# tdoa_4011_decotec.net
KiCad netlist of a schematic drawn in EAGLE
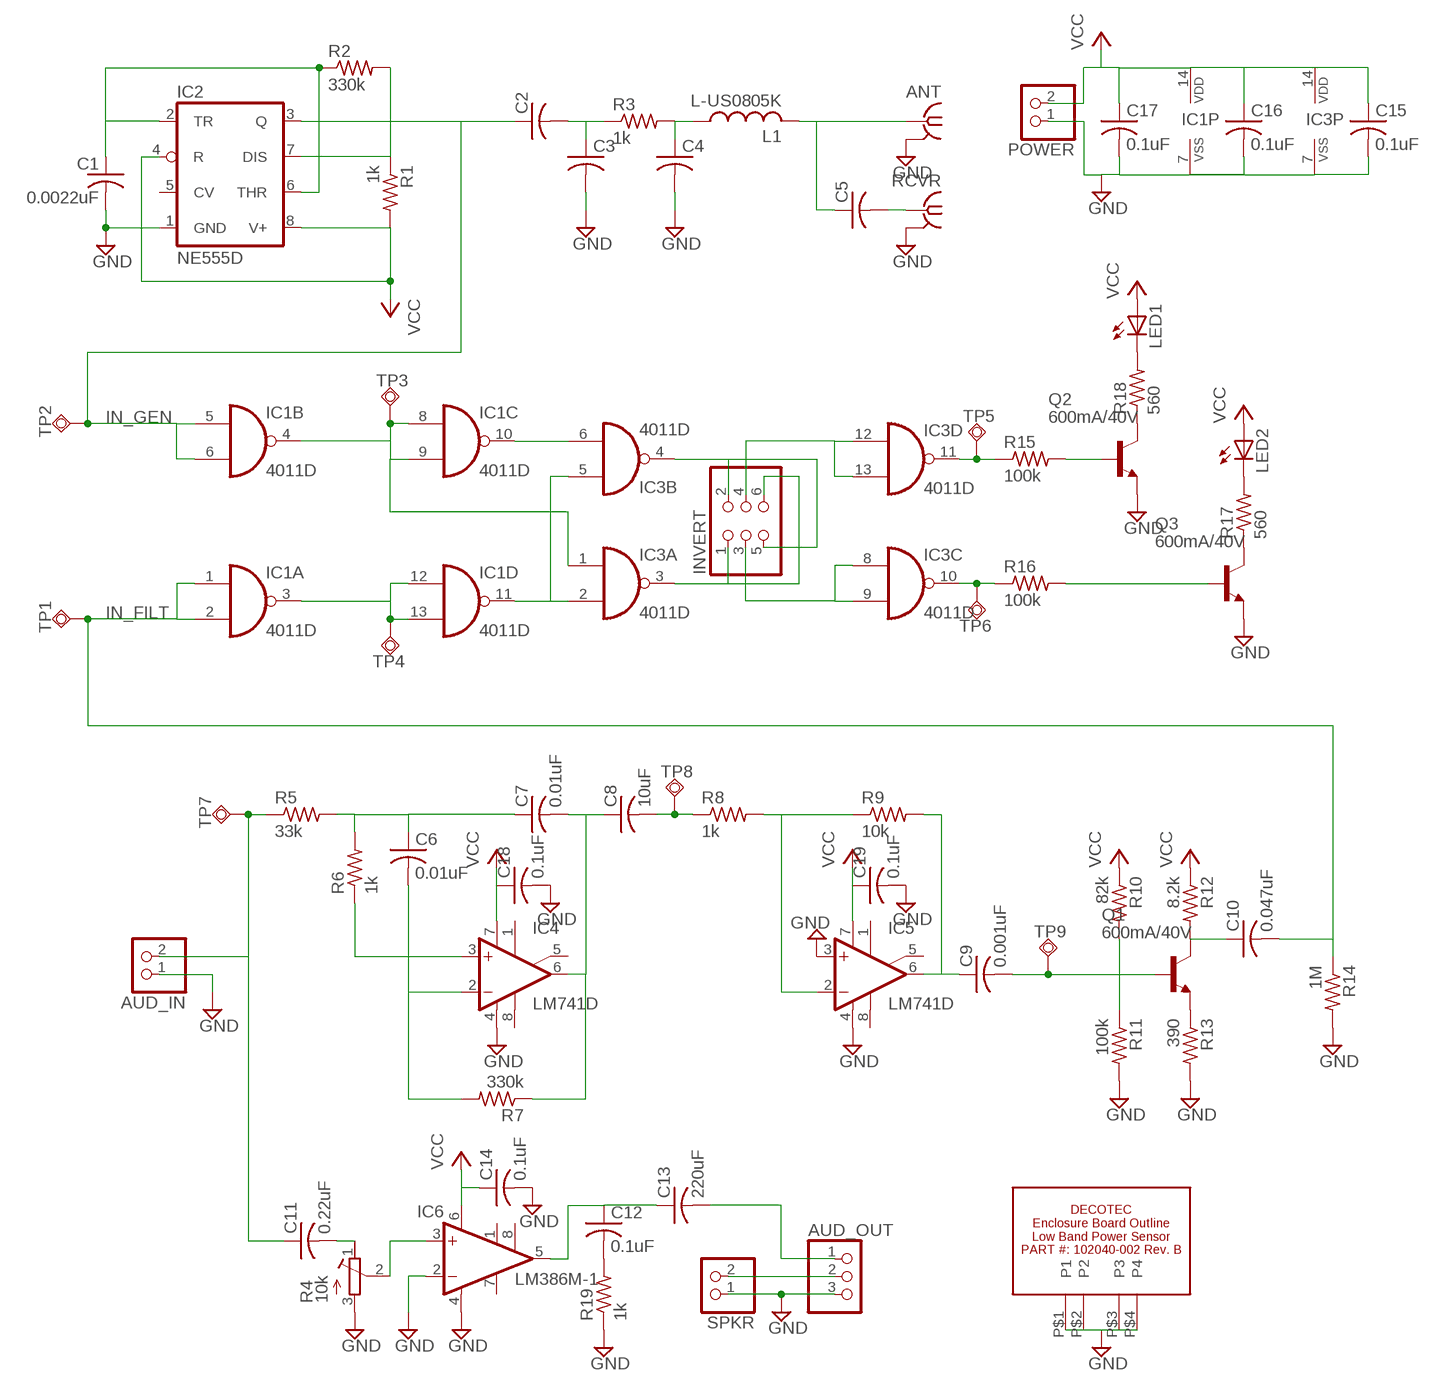
[diagram p0: schematic, sheet 1]

(export (version "E")
  (design (tool "Eeschema 10.0.6"))
  (components
    (comp (ref "ANT")
      (value "SMA-142-0701-801/806")
      (footprint "eagle-import:J502-ND-142-0701-801_806")
      (fields (field (name "MF") "JOHNSON COMPONENTS") (field (name "MPN") "142-0701-801"))
      (libsource (lib "eagle-import") (part "SMA-142-0701-801/806"))
    )
    (comp (ref "AUD_IN")
      (value "PINHD-1X2")
      (footprint "eagle-import:1X02")
      (libsource (lib "eagle-import") (part "PINHD-1X2"))
    )
    (comp (ref "AUD_OUT")
      (value "PINHD-1X3")
      (footprint "eagle-import:1X03")
      (libsource (lib "eagle-import") (part "PINHD-1X3"))
    )
    (comp (ref "C1")
      (value "0.0022uF")
      (footprint "eagle-import:C0805K")
      (libsource (lib "eagle-import") (part "C-USC0805K"))
    )
    (comp (ref "C2")
      (value "C-USC0805K")
      (footprint "eagle-import:C0805K")
      (libsource (lib "eagle-import") (part "C-USC0805K"))
    )
    (comp (ref "C3")
      (value "C-USC0805K")
      (footprint "eagle-import:C0805K")
      (libsource (lib "eagle-import") (part "C-USC0805K"))
    )
    (comp (ref "C4")
      (value "C-USC0805K")
      (footprint "eagle-import:C0805K")
      (libsource (lib "eagle-import") (part "C-USC0805K"))
    )
    (comp (ref "C5")
      (value "C-USC0805K")
      (footprint "eagle-import:C0805K")
      (libsource (lib "eagle-import") (part "C-USC0805K"))
    )
    (comp (ref "C6")
      (value "0.01uF")
      (footprint "eagle-import:C0805K")
      (libsource (lib "eagle-import") (part "C-USC0805K"))
    )
    (comp (ref "C7")
      (value "0.01uF")
      (footprint "eagle-import:C0805K")
      (libsource (lib "eagle-import") (part "C-USC0805K"))
    )
    (comp (ref "C8")
      (value "10uF")
      (footprint "eagle-import:C0805K")
      (libsource (lib "eagle-import") (part "C-USC0805K"))
    )
    (comp (ref "C9")
      (value "0.001uF")
      (footprint "eagle-import:C0805K")
      (libsource (lib "eagle-import") (part "C-USC0805K"))
    )
    (comp (ref "C10")
      (value "0.047uF")
      (footprint "eagle-import:C0805K")
      (libsource (lib "eagle-import") (part "C-USC0805K"))
    )
    (comp (ref "C11")
      (value "0.22uF")
      (footprint "eagle-import:C0805K")
      (libsource (lib "eagle-import") (part "C-USC0805K"))
    )
    (comp (ref "C12")
      (value "0.1uF")
      (footprint "eagle-import:C0805K")
      (libsource (lib "eagle-import") (part "C-USC0805K"))
    )
    (comp (ref "C13")
      (value "220uF")
      (footprint "eagle-import:C0805K")
      (libsource (lib "eagle-import") (part "C-USC0805K"))
    )
    (comp (ref "C14")
      (value "0.1uF")
      (footprint "eagle-import:C0805K")
      (libsource (lib "eagle-import") (part "C-USC0805K"))
    )
    (comp (ref "C15")
      (value "0.1uF")
      (footprint "eagle-import:C0805K")
      (libsource (lib "eagle-import") (part "C-USC0805K"))
    )
    (comp (ref "C16")
      (value "0.1uF")
      (footprint "eagle-import:C0805K")
      (libsource (lib "eagle-import") (part "C-USC0805K"))
    )
    (comp (ref "C17")
      (value "0.1uF")
      (footprint "eagle-import:C0805K")
      (libsource (lib "eagle-import") (part "C-USC0805K"))
    )
    (comp (ref "C18")
      (value "0.1uF")
      (footprint "eagle-import:C0805K")
      (libsource (lib "eagle-import") (part "C-USC0805K"))
    )
    (comp (ref "C19")
      (value "0.1uF")
      (footprint "eagle-import:C0805K")
      (libsource (lib "eagle-import") (part "C-USC0805K"))
    )
    (comp (ref "IC1")
      (value "4011D")
      (footprint "eagle-import:SO14")
      (libsource (lib "eagle-import") (part "4011D"))
    )
    (comp (ref "IC2")
      (value "NE555D")
      (footprint "eagle-import:SO08")
      (libsource (lib "eagle-import") (part "555DNE"))
    )
    (comp (ref "IC3")
      (value "4011D")
      (footprint "eagle-import:SO14")
      (libsource (lib "eagle-import") (part "4011D"))
    )
    (comp (ref "IC4")
      (value "LM741D")
      (footprint "eagle-import:SO08")
      (libsource (lib "eagle-import") (part "741DLM"))
    )
    (comp (ref "IC5")
      (value "LM741D")
      (footprint "eagle-import:SO08")
      (libsource (lib "eagle-import") (part "741DLM"))
    )
    (comp (ref "IC6")
      (value "LM386M-1")
      (footprint "eagle-import:SO08")
      (libsource (lib "eagle-import") (part "LM386?-M1"))
    )
    (comp (ref "INVERT")
      (value "PINHD-2X3")
      (footprint "eagle-import:2X03")
      (libsource (lib "eagle-import") (part "PINHD-2X3"))
    )
    (comp (ref "L1")
      (value "L-US0805K")
      (footprint "eagle-import:C0805K")
      (libsource (lib "eagle-import") (part "L-US0805K"))
    )
    (comp (ref "LED1")
      (value "LED3MM")
      (footprint "eagle-import:LED3MM")
      (libsource (lib "eagle-import") (part "LED3MM"))
    )
    (comp (ref "LED2")
      (value "LED3MM")
      (footprint "eagle-import:LED3MM")
      (libsource (lib "eagle-import") (part "LED3MM"))
    )
    (comp (ref "POWER")
      (value "PINHD-1X2")
      (footprint "eagle-import:1X02")
      (libsource (lib "eagle-import") (part "PINHD-1X2"))
    )
    (comp (ref "Q1")
      (value "600mA/40V")
      (footprint "eagle-import:SOT23-BEC")
      (libsource (lib "eagle-import") (part "-NPN-SOT23-BECMMBT3904LT1"))
    )
    (comp (ref "Q2")
      (value "600mA/40V")
      (footprint "eagle-import:SOT23-BEC")
      (libsource (lib "eagle-import") (part "-NPN-SOT23-BECMMBT3904LT1"))
    )
    (comp (ref "Q3")
      (value "600mA/40V")
      (footprint "eagle-import:SOT23-BEC")
      (libsource (lib "eagle-import") (part "-NPN-SOT23-BECMMBT3904LT1"))
    )
    (comp (ref "R1")
      (value "1k")
      (footprint "eagle-import:R0805")
      (libsource (lib "eagle-import") (part "R-US_R0805"))
    )
    (comp (ref "R2")
      (value "330k")
      (footprint "eagle-import:R0805")
      (libsource (lib "eagle-import") (part "R-US_R0805"))
    )
    (comp (ref "R3")
      (value "1k")
      (footprint "eagle-import:R0805")
      (libsource (lib "eagle-import") (part "R-US_R0805"))
    )
    (comp (ref "R4")
      (value "10k")
      (footprint "eagle-import:RTRIM3314G")
      (libsource (lib "eagle-import") (part "R-TRIMM3314G"))
    )
    (comp (ref "R5")
      (value "33k")
      (footprint "eagle-import:R0805")
      (libsource (lib "eagle-import") (part "R-US_R0805"))
    )
    (comp (ref "R6")
      (value "1k")
      (footprint "eagle-import:R0805")
      (libsource (lib "eagle-import") (part "R-US_R0805"))
    )
    (comp (ref "R7")
      (value "330k")
      (footprint "eagle-import:R0805")
      (libsource (lib "eagle-import") (part "R-US_R0805"))
    )
    (comp (ref "R8")
      (value "1k")
      (footprint "eagle-import:R0805")
      (libsource (lib "eagle-import") (part "R-US_R0805"))
    )
    (comp (ref "R9")
      (value "10k")
      (footprint "eagle-import:R0805")
      (libsource (lib "eagle-import") (part "R-US_R0805"))
    )
    (comp (ref "R10")
      (value "82k")
      (footprint "eagle-import:R0805")
      (libsource (lib "eagle-import") (part "R-US_R0805"))
    )
    (comp (ref "R11")
      (value "100k")
      (footprint "eagle-import:R0805")
      (libsource (lib "eagle-import") (part "R-US_R0805"))
    )
    (comp (ref "R12")
      (value "8.2k")
      (footprint "eagle-import:R0805")
      (libsource (lib "eagle-import") (part "R-US_R0805"))
    )
    (comp (ref "R13")
      (value "390")
      (footprint "eagle-import:R0805")
      (libsource (lib "eagle-import") (part "R-US_R0805"))
    )
    (comp (ref "R14")
      (value "1M")
      (footprint "eagle-import:R0805")
      (libsource (lib "eagle-import") (part "R-US_R0805"))
    )
    (comp (ref "R15")
      (value "100k")
      (footprint "eagle-import:R0805")
      (libsource (lib "eagle-import") (part "R-US_R0805"))
    )
    (comp (ref "R16")
      (value "100k")
      (footprint "eagle-import:R0805")
      (libsource (lib "eagle-import") (part "R-US_R0805"))
    )
    (comp (ref "R17")
      (value "560")
      (footprint "eagle-import:R0805")
      (libsource (lib "eagle-import") (part "R-US_R0805"))
    )
    (comp (ref "R18")
      (value "560")
      (footprint "eagle-import:R0805")
      (libsource (lib "eagle-import") (part "R-US_R0805"))
    )
    (comp (ref "R19")
      (value "1k")
      (footprint "eagle-import:R0805")
      (libsource (lib "eagle-import") (part "R-US_R0805"))
    )
    (comp (ref "RCVR")
      (value "SMA-142-0701-801/806")
      (footprint "eagle-import:J502-ND-142-0701-801_806")
      (fields (field (name "MF") "JOHNSON COMPONENTS") (field (name "MPN") "142-0701-801"))
      (libsource (lib "eagle-import") (part "SMA-142-0701-801/806"))
    )
    (comp (ref "SPKR")
      (value "PINHD-1X2")
      (footprint "eagle-import:1X02")
      (libsource (lib "eagle-import") (part "PINHD-1X2"))
    )
    (comp (ref "TP1")
      (value "TPSQTP20SQ")
      (footprint "eagle-import:TP20SQ")
      (libsource (lib "eagle-import") (part "TPSQTP20SQ"))
    )
    (comp (ref "TP2")
      (value "TPSQTP20SQ")
      (footprint "eagle-import:TP20SQ")
      (libsource (lib "eagle-import") (part "TPSQTP20SQ"))
    )
    (comp (ref "TP3")
      (value "TPSQTP20SQ")
      (footprint "eagle-import:TP20SQ")
      (libsource (lib "eagle-import") (part "TPSQTP20SQ"))
    )
    (comp (ref "TP4")
      (value "TPSQTP20SQ")
      (footprint "eagle-import:TP20SQ")
      (libsource (lib "eagle-import") (part "TPSQTP20SQ"))
    )
    (comp (ref "TP5")
      (value "TPSQTP20SQ")
      (footprint "eagle-import:TP20SQ")
      (libsource (lib "eagle-import") (part "TPSQTP20SQ"))
    )
    (comp (ref "TP6")
      (value "TPSQTP20SQ")
      (footprint "eagle-import:TP20SQ")
      (libsource (lib "eagle-import") (part "TPSQTP20SQ"))
    )
    (comp (ref "TP7")
      (value "TPSQTP20SQ")
      (footprint "eagle-import:TP20SQ")
      (libsource (lib "eagle-import") (part "TPSQTP20SQ"))
    )
    (comp (ref "TP8")
      (value "TPSQTP20SQ")
      (footprint "eagle-import:TP20SQ")
      (libsource (lib "eagle-import") (part "TPSQTP20SQ"))
    )
    (comp (ref "TP9")
      (value "TPSQTP20SQ")
      (footprint "eagle-import:TP20SQ")
      (libsource (lib "eagle-import") (part "TPSQTP20SQ"))
    )
    (comp (ref "U$1")
      (value "DECOTEC_102040-002B")
      (footprint "eagle-import:DECOTEC_102040-002B")
      (libsource (lib "eagle-import") (part "DECOTEC_102040-002B"))
    )
  )
  (nets
    (net (code "1") (name "/IN_FILT") (class "Default")
      (node (ref "C10") (pin "2") (pinfunction "2_2") (pintype "passive"))
      (node (ref "IC1") (pin "1") (pinfunction "I0_1") (pintype "input"))
      (node (ref "IC1") (pin "2") (pinfunction "I1_2") (pintype "input"))
      (node (ref "R14") (pin "1") (pinfunction "1_1") (pintype "passive"))
      (node (ref "TP1") (pin "TP") (pinfunction "TP_TP") (pintype "input"))
    )
    (net (code "2") (name "/IN_GEN") (class "Default")
      (node (ref "C2") (pin "1") (pinfunction "1_1") (pintype "passive"))
      (node (ref "IC1") (pin "5") (pinfunction "I0_5") (pintype "input"))
      (node (ref "IC1") (pin "6") (pinfunction "I1_6") (pintype "input"))
      (node (ref "IC2") (pin "3") (pinfunction "Q_3") (pintype "output"))
      (node (ref "TP2") (pin "TP") (pinfunction "TP_TP") (pintype "input"))
    )
    (net (code "3") (name "GND") (class "Default")
      (node (ref "ANT") (pin "G@1") (pinfunction "2_G@1") (pintype "passive"))
      (node (ref "ANT") (pin "G@2") (pinfunction "2_G@2") (pintype "passive"))
      (node (ref "ANT") (pin "G@3") (pinfunction "2_G@3") (pintype "passive"))
      (node (ref "ANT") (pin "G@4") (pinfunction "2_G@4") (pintype "passive"))
      (node (ref "AUD_IN") (pin "1") (pinfunction "1_1") (pintype "passive"))
      (node (ref "AUD_OUT") (pin "3") (pinfunction "3_3") (pintype "passive"))
      (node (ref "C1") (pin "2") (pinfunction "2_2") (pintype "passive"))
      (node (ref "C14") (pin "2") (pinfunction "2_2") (pintype "passive"))
      (node (ref "C15") (pin "2") (pinfunction "2_2") (pintype "passive"))
      (node (ref "C16") (pin "2") (pinfunction "2_2") (pintype "passive"))
      (node (ref "C17") (pin "2") (pinfunction "2_2") (pintype "passive"))
      (node (ref "C18") (pin "2") (pinfunction "2_2") (pintype "passive"))
      (node (ref "C19") (pin "2") (pinfunction "2_2") (pintype "passive"))
      (node (ref "C3") (pin "2") (pinfunction "2_2") (pintype "passive"))
      (node (ref "C4") (pin "2") (pinfunction "2_2") (pintype "passive"))
      (node (ref "IC1") (pin "7") (pinfunction "VSS_7") (pintype "power_in"))
      (node (ref "IC2") (pin "1") (pinfunction "GND_1") (pintype "power_in"))
      (node (ref "IC3") (pin "7") (pinfunction "VSS_7") (pintype "power_in"))
      (node (ref "IC4") (pin "4") (pinfunction "V-_4") (pintype "power_in"))
      (node (ref "IC5") (pin "3") (pinfunction "+IN_3") (pintype "input"))
      (node (ref "IC5") (pin "4") (pinfunction "V-_4") (pintype "power_in"))
      (node (ref "IC6") (pin "2") (pinfunction "-IN_2") (pintype "input"))
      (node (ref "IC6") (pin "4") (pinfunction "GND_4") (pintype "power_in"))
      (node (ref "POWER") (pin "1") (pinfunction "1_1") (pintype "passive"))
      (node (ref "Q2") (pin "E") (pinfunction "E_E") (pintype "passive"))
      (node (ref "Q3") (pin "E") (pinfunction "E_E") (pintype "passive"))
      (node (ref "R11") (pin "2") (pinfunction "2_2") (pintype "passive"))
      (node (ref "R13") (pin "2") (pinfunction "2_2") (pintype "passive"))
      (node (ref "R14") (pin "2") (pinfunction "2_2") (pintype "passive"))
      (node (ref "R19") (pin "1") (pinfunction "1_1") (pintype "passive"))
      (node (ref "R4") (pin "3") (pinfunction "A_3") (pintype "passive"))
      (node (ref "RCVR") (pin "G@1") (pinfunction "2_G@1") (pintype "passive"))
      (node (ref "RCVR") (pin "G@2") (pinfunction "2_G@2") (pintype "passive"))
      (node (ref "RCVR") (pin "G@3") (pinfunction "2_G@3") (pintype "passive"))
      (node (ref "RCVR") (pin "G@4") (pinfunction "2_G@4") (pintype "passive"))
      (node (ref "SPKR") (pin "1") (pinfunction "1_1") (pintype "passive"))
      (node (ref "U$1") (pin "P$1") (pinfunction "P1_P$1") (pintype "bidirectional"))
      (node (ref "U$1") (pin "P$2") (pinfunction "P2_P$2") (pintype "bidirectional"))
      (node (ref "U$1") (pin "P$3") (pinfunction "P3_P$3") (pintype "bidirectional"))
      (node (ref "U$1") (pin "P$4") (pinfunction "P4_P$4") (pintype "bidirectional"))
    )
    (net (code "4") (name "Net-(ANT-Pad1)") (class "Default")
      (node (ref "ANT") (pin "1") (pinfunction "1_1") (pintype "passive"))
      (node (ref "C5") (pin "1") (pinfunction "1_1") (pintype "passive"))
      (node (ref "L1") (pin "2") (pinfunction "2_2") (pintype "passive"))
    )
    (net (code "5") (name "Net-(AUD_IN-Pad2)") (class "Default")
      (node (ref "AUD_IN") (pin "2") (pinfunction "2_2") (pintype "passive"))
      (node (ref "C11") (pin "1") (pinfunction "1_1") (pintype "passive"))
      (node (ref "R5") (pin "1") (pinfunction "1_1") (pintype "passive"))
      (node (ref "TP7") (pin "TP") (pinfunction "TP_TP") (pintype "input"))
    )
    (net (code "6") (name "Net-(AUD_OUT-Pad1)") (class "Default")
      (node (ref "AUD_OUT") (pin "1") (pinfunction "1_1") (pintype "passive"))
      (node (ref "C13") (pin "2") (pinfunction "2_2") (pintype "passive"))
    )
    (net (code "7") (name "Net-(AUD_OUT-Pad2)") (class "Default")
      (node (ref "AUD_OUT") (pin "2") (pinfunction "2_2") (pintype "passive"))
      (node (ref "SPKR") (pin "2") (pinfunction "2_2") (pintype "passive"))
    )
    (net (code "8") (name "Net-(C2-Pad2)") (class "Default")
      (node (ref "C2") (pin "2") (pinfunction "2_2") (pintype "passive"))
      (node (ref "C3") (pin "1") (pinfunction "1_1") (pintype "passive"))
      (node (ref "R3") (pin "1") (pinfunction "1_1") (pintype "passive"))
    )
    (net (code "9") (name "Net-(C4-Pad1)") (class "Default")
      (node (ref "C4") (pin "1") (pinfunction "1_1") (pintype "passive"))
      (node (ref "L1") (pin "1") (pinfunction "1_1") (pintype "passive"))
      (node (ref "R3") (pin "2") (pinfunction "2_2") (pintype "passive"))
    )
    (net (code "10") (name "Net-(C5-Pad2)") (class "Default")
      (node (ref "C5") (pin "2") (pinfunction "2_2") (pintype "passive"))
      (node (ref "RCVR") (pin "1") (pinfunction "1_1") (pintype "passive"))
    )
    (net (code "11") (name "Net-(C6-Pad1)") (class "Default")
      (node (ref "C6") (pin "1") (pinfunction "1_1") (pintype "passive"))
      (node (ref "C7") (pin "1") (pinfunction "1_1") (pintype "passive"))
      (node (ref "R5") (pin "2") (pinfunction "2_2") (pintype "passive"))
      (node (ref "R6") (pin "2") (pinfunction "2_2") (pintype "passive"))
    )
    (net (code "12") (name "Net-(C8-Pad2)") (class "Default")
      (node (ref "C8") (pin "2") (pinfunction "2_2") (pintype "passive"))
      (node (ref "R8") (pin "1") (pinfunction "1_1") (pintype "passive"))
      (node (ref "TP8") (pin "TP") (pinfunction "TP_TP") (pintype "input"))
    )
    (net (code "13") (name "Net-(C9-Pad2)") (class "Default")
      (node (ref "C9") (pin "2") (pinfunction "2_2") (pintype "passive"))
      (node (ref "Q1") (pin "B") (pinfunction "B_B") (pintype "passive"))
      (node (ref "R10") (pin "2") (pinfunction "2_2") (pintype "passive"))
      (node (ref "R11") (pin "1") (pinfunction "1_1") (pintype "passive"))
      (node (ref "TP9") (pin "TP") (pinfunction "TP_TP") (pintype "input"))
    )
    (net (code "14") (name "Net-(C10-Pad1)") (class "Default")
      (node (ref "C10") (pin "1") (pinfunction "1_1") (pintype "passive"))
      (node (ref "Q1") (pin "C") (pinfunction "C_C") (pintype "passive"))
      (node (ref "R12") (pin "2") (pinfunction "2_2") (pintype "passive"))
    )
    (net (code "15") (name "Net-(C12-Pad2)") (class "Default")
      (node (ref "C12") (pin "2") (pinfunction "2_2") (pintype "passive"))
      (node (ref "R19") (pin "2") (pinfunction "2_2") (pintype "passive"))
    )
    (net (code "16") (name "Net-(IC1A-O)") (class "Default")
      (node (ref "IC1") (pin "12") (pinfunction "I0_12") (pintype "input"))
      (node (ref "IC1") (pin "13") (pinfunction "I1_13") (pintype "input"))
      (node (ref "IC1") (pin "3") (pinfunction "O_3") (pintype "output"))
      (node (ref "TP4") (pin "TP") (pinfunction "TP_TP") (pintype "input"))
    )
    (net (code "17") (name "Net-(IC1B-O)") (class "Default")
      (node (ref "IC1") (pin "4") (pinfunction "O_4") (pintype "output"))
      (node (ref "IC1") (pin "8") (pinfunction "I0_8") (pintype "input"))
      (node (ref "IC1") (pin "9") (pinfunction "I1_9") (pintype "input"))
      (node (ref "IC3") (pin "1") (pinfunction "I0_1") (pintype "input"))
      (node (ref "TP3") (pin "TP") (pinfunction "TP_TP") (pintype "input"))
    )
    (net (code "18") (name "Net-(IC1C-O)") (class "Default")
      (node (ref "IC1") (pin "10") (pinfunction "O_10") (pintype "output"))
      (node (ref "IC3") (pin "6") (pinfunction "I1_6") (pintype "input"))
    )
    (net (code "19") (name "Net-(IC1D-O)") (class "Default")
      (node (ref "IC1") (pin "11") (pinfunction "O_11") (pintype "output"))
      (node (ref "IC3") (pin "2") (pinfunction "I1_2") (pintype "input"))
      (node (ref "IC3") (pin "5") (pinfunction "I0_5") (pintype "input"))
    )
    (net (code "20") (name "Net-(IC2-DIS)") (class "Default")
      (node (ref "IC2") (pin "7") (pinfunction "DIS_7") (pintype "input"))
      (node (ref "R1") (pin "1") (pinfunction "1_1") (pintype "passive"))
      (node (ref "R2") (pin "2") (pinfunction "2_2") (pintype "passive"))
    )
    (net (code "21") (name "Net-(IC2-THR)") (class "Default")
      (node (ref "C1") (pin "1") (pinfunction "1_1") (pintype "passive"))
      (node (ref "IC2") (pin "2") (pinfunction "TR_2") (pintype "input"))
      (node (ref "IC2") (pin "6") (pinfunction "THR_6") (pintype "input"))
      (node (ref "R2") (pin "1") (pinfunction "1_1") (pintype "passive"))
    )
    (net (code "22") (name "Net-(IC3A-O)") (class "Default")
      (node (ref "IC3") (pin "3") (pinfunction "O_3") (pintype "output"))
      (node (ref "INVERT") (pin "1") (pinfunction "1_1") (pintype "passive"))
      (node (ref "INVERT") (pin "6") (pinfunction "6_6") (pintype "passive"))
    )
    (net (code "23") (name "Net-(IC3B-O)") (class "Default")
      (node (ref "IC3") (pin "4") (pinfunction "O_4") (pintype "output"))
      (node (ref "INVERT") (pin "2") (pinfunction "2_2") (pintype "passive"))
      (node (ref "INVERT") (pin "5") (pinfunction "5_5") (pintype "passive"))
    )
    (net (code "24") (name "Net-(IC3C-I0)") (class "Default")
      (node (ref "IC3") (pin "8") (pinfunction "I0_8") (pintype "input"))
      (node (ref "IC3") (pin "9") (pinfunction "I1_9") (pintype "input"))
      (node (ref "INVERT") (pin "3") (pinfunction "3_3") (pintype "passive"))
    )
    (net (code "25") (name "Net-(IC3C-O)") (class "Default")
      (node (ref "IC3") (pin "10") (pinfunction "O_10") (pintype "output"))
      (node (ref "R16") (pin "1") (pinfunction "1_1") (pintype "passive"))
      (node (ref "TP6") (pin "TP") (pinfunction "TP_TP") (pintype "input"))
    )
    (net (code "26") (name "Net-(IC3D-I0)") (class "Default")
      (node (ref "IC3") (pin "12") (pinfunction "I0_12") (pintype "input"))
      (node (ref "IC3") (pin "13") (pinfunction "I1_13") (pintype "input"))
      (node (ref "INVERT") (pin "4") (pinfunction "4_4") (pintype "passive"))
    )
    (net (code "27") (name "Net-(IC3D-O)") (class "Default")
      (node (ref "IC3") (pin "11") (pinfunction "O_11") (pintype "output"))
      (node (ref "R15") (pin "1") (pinfunction "1_1") (pintype "passive"))
      (node (ref "TP5") (pin "TP") (pinfunction "TP_TP") (pintype "input"))
    )
    (net (code "28") (name "Net-(IC4-+IN)") (class "Default")
      (node (ref "IC4") (pin "3") (pinfunction "+IN_3") (pintype "input"))
      (node (ref "R6") (pin "1") (pinfunction "1_1") (pintype "passive"))
    )
    (net (code "29") (name "Net-(IC4--IN)") (class "Default")
      (node (ref "C6") (pin "2") (pinfunction "2_2") (pintype "passive"))
      (node (ref "IC4") (pin "2") (pinfunction "-IN_2") (pintype "input"))
      (node (ref "R7") (pin "2") (pinfunction "2_2") (pintype "passive"))
    )
    (net (code "30") (name "Net-(IC4-OUT)") (class "Default")
      (node (ref "C7") (pin "2") (pinfunction "2_2") (pintype "passive"))
      (node (ref "C8") (pin "1") (pinfunction "1_1") (pintype "passive"))
      (node (ref "IC4") (pin "6") (pinfunction "OUT_6") (pintype "output"))
      (node (ref "R7") (pin "1") (pinfunction "1_1") (pintype "passive"))
    )
    (net (code "31") (name "Net-(IC5--IN)") (class "Default")
      (node (ref "IC5") (pin "2") (pinfunction "-IN_2") (pintype "input"))
      (node (ref "R8") (pin "2") (pinfunction "2_2") (pintype "passive"))
      (node (ref "R9") (pin "1") (pinfunction "1_1") (pintype "passive"))
    )
    (net (code "32") (name "Net-(IC5-OUT)") (class "Default")
      (node (ref "C9") (pin "1") (pinfunction "1_1") (pintype "passive"))
      (node (ref "IC5") (pin "6") (pinfunction "OUT_6") (pintype "output"))
      (node (ref "R9") (pin "2") (pinfunction "2_2") (pintype "passive"))
    )
    (net (code "33") (name "Net-(IC6-+IN)") (class "Default")
      (node (ref "IC6") (pin "3") (pinfunction "+IN_3") (pintype "input"))
      (node (ref "R4") (pin "2") (pinfunction "S_2") (pintype "passive"))
    )
    (net (code "34") (name "Net-(IC6-OUT)") (class "Default")
      (node (ref "C12") (pin "1") (pinfunction "1_1") (pintype "passive"))
      (node (ref "C13") (pin "1") (pinfunction "1_1") (pintype "passive"))
      (node (ref "IC6") (pin "5") (pinfunction "OUT_5") (pintype "output"))
    )
    (net (code "35") (name "Net-(LED1-C)") (class "Default")
      (node (ref "LED1") (pin "K") (pinfunction "C_K") (pintype "passive"))
      (node (ref "R18") (pin "2") (pinfunction "2_2") (pintype "passive"))
    )
    (net (code "36") (name "Net-(LED2-C)") (class "Default")
      (node (ref "LED2") (pin "K") (pinfunction "C_K") (pintype "passive"))
      (node (ref "R17") (pin "2") (pinfunction "2_2") (pintype "passive"))
    )
    (net (code "37") (name "Net-(Q1-PadE)") (class "Default")
      (node (ref "Q1") (pin "E") (pinfunction "E_E") (pintype "passive"))
      (node (ref "R13") (pin "1") (pinfunction "1_1") (pintype "passive"))
    )
    (net (code "38") (name "Net-(Q2-PadB)") (class "Default")
      (node (ref "Q2") (pin "B") (pinfunction "B_B") (pintype "passive"))
      (node (ref "R15") (pin "2") (pinfunction "2_2") (pintype "passive"))
    )
    (net (code "39") (name "Net-(Q2-PadC)") (class "Default")
      (node (ref "Q2") (pin "C") (pinfunction "C_C") (pintype "passive"))
      (node (ref "R18") (pin "1") (pinfunction "1_1") (pintype "passive"))
    )
    (net (code "40") (name "Net-(Q3-PadB)") (class "Default")
      (node (ref "Q3") (pin "B") (pinfunction "B_B") (pintype "passive"))
      (node (ref "R16") (pin "2") (pinfunction "2_2") (pintype "passive"))
    )
    (net (code "41") (name "Net-(Q3-PadC)") (class "Default")
      (node (ref "Q3") (pin "C") (pinfunction "C_C") (pintype "passive"))
      (node (ref "R17") (pin "1") (pinfunction "1_1") (pintype "passive"))
    )
    (net (code "42") (name "Net-(R4-E)") (class "Default")
      (node (ref "C11") (pin "2") (pinfunction "2_2") (pintype "passive"))
      (node (ref "R4") (pin "1") (pinfunction "E_1") (pintype "passive"))
    )
    (net (code "43") (name "VCC") (class "Default")
      (node (ref "C14") (pin "1") (pinfunction "1_1") (pintype "passive"))
      (node (ref "C15") (pin "1") (pinfunction "1_1") (pintype "passive"))
      (node (ref "C16") (pin "1") (pinfunction "1_1") (pintype "passive"))
      (node (ref "C17") (pin "1") (pinfunction "1_1") (pintype "passive"))
      (node (ref "C18") (pin "1") (pinfunction "1_1") (pintype "passive"))
      (node (ref "C19") (pin "1") (pinfunction "1_1") (pintype "passive"))
      (node (ref "IC1") (pin "14") (pinfunction "VDD_14") (pintype "power_in"))
      (node (ref "IC2") (pin "4") (pinfunction "R_4") (pintype "input"))
      (node (ref "IC2") (pin "8") (pinfunction "V+_8") (pintype "power_in"))
      (node (ref "IC3") (pin "14") (pinfunction "VDD_14") (pintype "power_in"))
      (node (ref "IC4") (pin "7") (pinfunction "V+_7") (pintype "power_in"))
      (node (ref "IC5") (pin "7") (pinfunction "V+_7") (pintype "power_in"))
      (node (ref "IC6") (pin "6") (pinfunction "VS_6") (pintype "power_in"))
      (node (ref "LED1") (pin "A") (pinfunction "A_A") (pintype "passive"))
      (node (ref "LED2") (pin "A") (pinfunction "A_A") (pintype "passive"))
      (node (ref "POWER") (pin "2") (pinfunction "2_2") (pintype "passive"))
      (node (ref "R1") (pin "2") (pinfunction "2_2") (pintype "passive"))
      (node (ref "R10") (pin "1") (pinfunction "1_1") (pintype "passive"))
      (node (ref "R12") (pin "1") (pinfunction "1_1") (pintype "passive"))
    )
    (net (code "44") (name "unconnected-(IC2-CV-Pad5)") (class "Default")
      (node (ref "IC2") (pin "5") (pinfunction "CV_5") (pintype "input"))
    )
    (net (code "45") (name "unconnected-(IC4-ON1-Pad1)") (class "Default")
      (node (ref "IC4") (pin "1") (pinfunction "ON1_1") (pintype "passive"))
    )
    (net (code "46") (name "unconnected-(IC4-ON2-Pad5)") (class "Default")
      (node (ref "IC4") (pin "5") (pinfunction "ON2_5") (pintype "passive"))
    )
    (net (code "47") (name "unconnected-(IC4-OPT-Pad8)") (class "Default")
      (node (ref "IC4") (pin "8") (pinfunction "OPT_8") (pintype "passive"))
    )
    (net (code "48") (name "unconnected-(IC5-ON1-Pad1)") (class "Default")
      (node (ref "IC5") (pin "1") (pinfunction "ON1_1") (pintype "passive"))
    )
    (net (code "49") (name "unconnected-(IC5-ON2-Pad5)") (class "Default")
      (node (ref "IC5") (pin "5") (pinfunction "ON2_5") (pintype "passive"))
    )
    (net (code "50") (name "unconnected-(IC5-OPT-Pad8)") (class "Default")
      (node (ref "IC5") (pin "8") (pinfunction "OPT_8") (pintype "passive"))
    )
    (net (code "51") (name "unconnected-(IC6-BYPASS-Pad7)") (class "Default")
      (node (ref "IC6") (pin "7") (pinfunction "BYPASS_7") (pintype "passive"))
    )
    (net (code "52") (name "unconnected-(IC6-GAIN-Pad1)") (class "Default")
      (node (ref "IC6") (pin "1") (pinfunction "GAIN_1") (pintype "passive"))
    )
    (net (code "53") (name "unconnected-(IC6-GAIN-Pad8)") (class "Default")
      (node (ref "IC6") (pin "8") (pinfunction "GAIN_8") (pintype "passive"))
    )
  )
)
